# TSat0-AvionicsPCB_v12.net
KiCad netlist of a schematic drawn in EAGLE
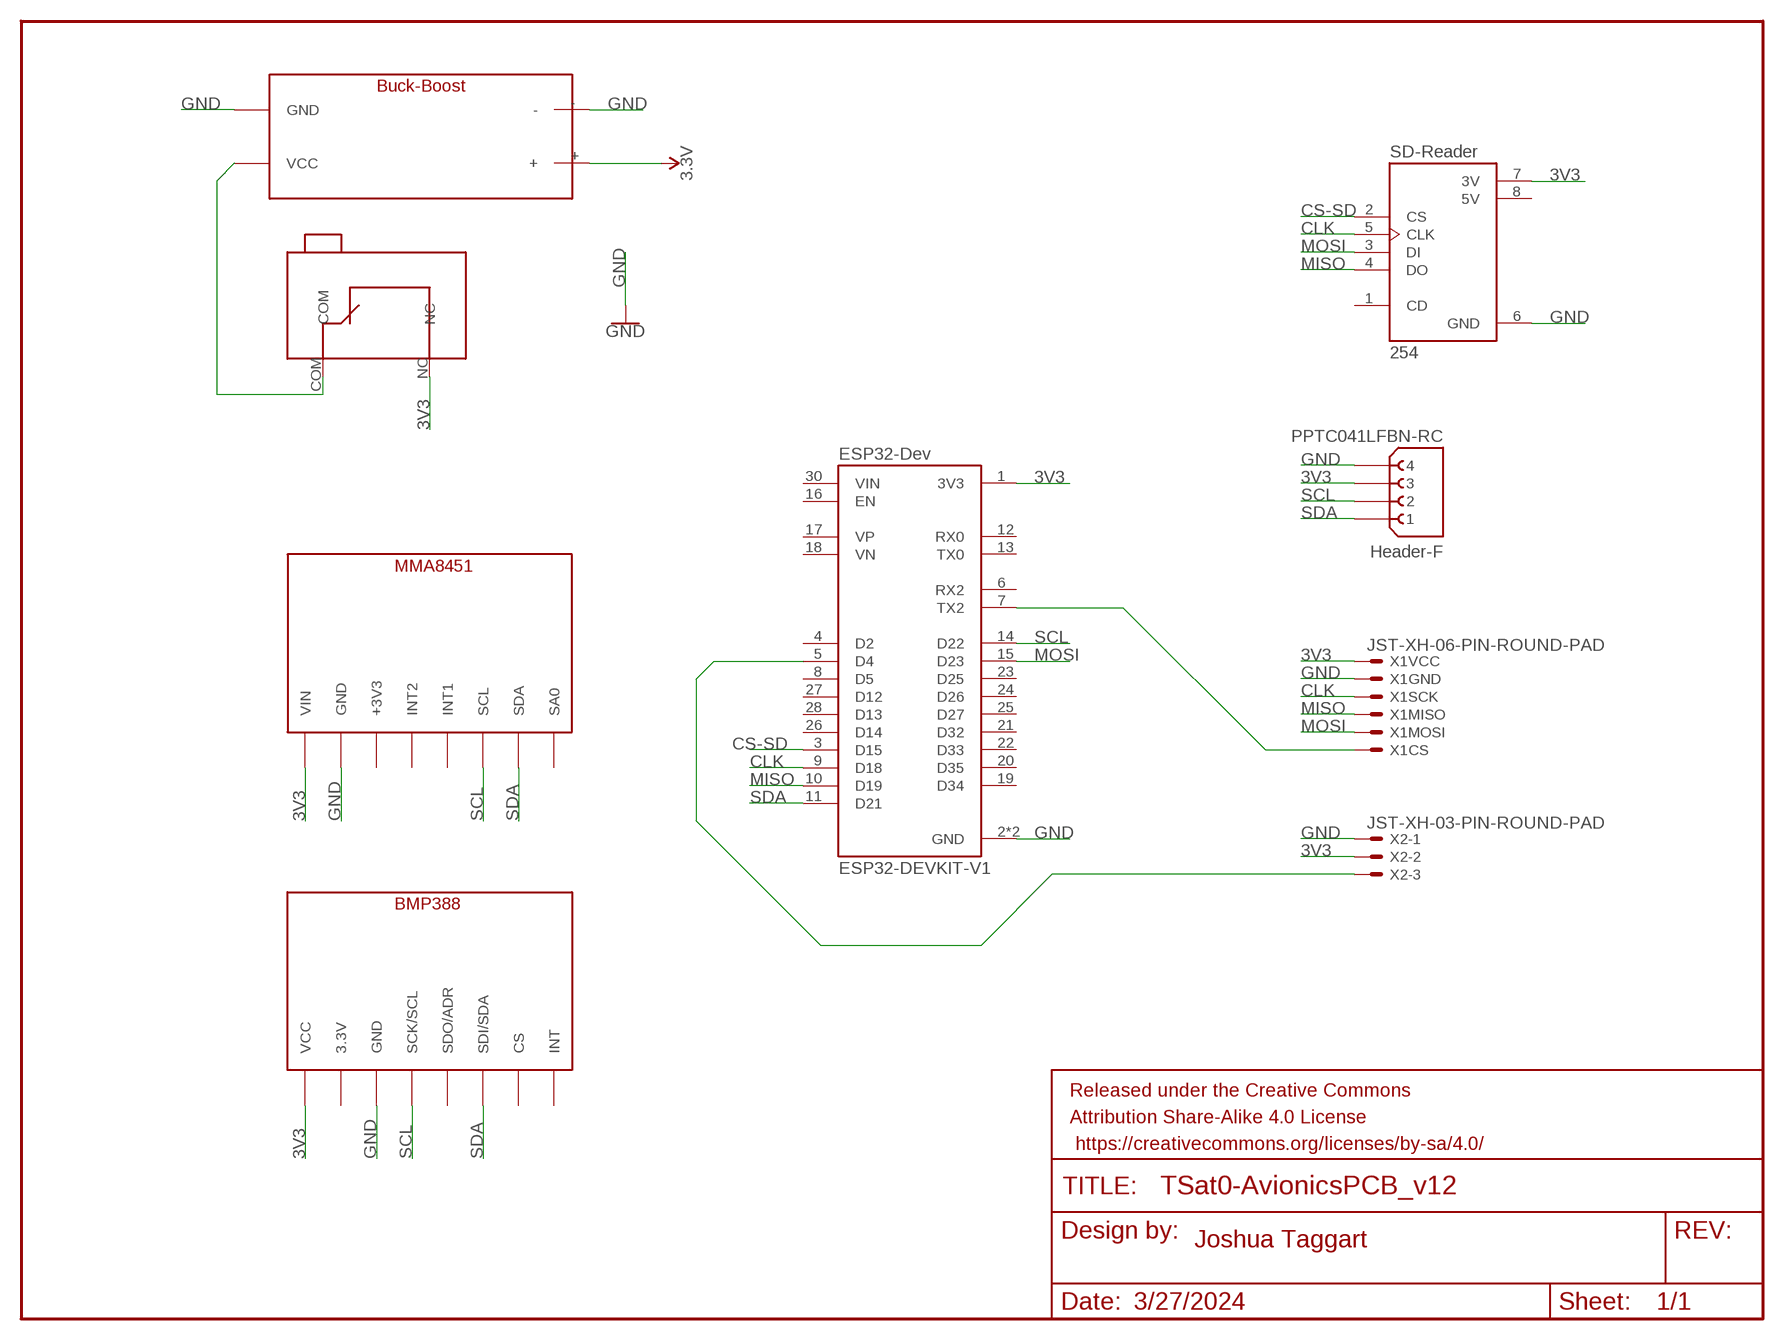
[diagram p0: schematic, sheet 1]

(export (version "E")
  (design (tool "Eeschema 10.0.6"))
  (components
    (comp (ref "BMP388")
      (value "BMP388")
      (footprint "eagle-import:BMP388-FP")
      (libsource (lib "eagle-import") (part "BMP388"))
    )
    (comp (ref "FRAME1")
      (value "FRAME-LETTERNO_PACKAGE")
      (footprint "eagle-import:DUMMY")
      (fields (field (name "DESIGNER") "Nobody"))
      (libsource (lib "eagle-import") (part "FRAME-LETTERNO_PACKAGE"))
    )
    (comp (ref "J1")
      (value "PPTC041LFBN-RC")
      (footprint "eagle-import:SULLINS_PPTC041LFBN-RC")
      (fields (field (name "MF") "Sullins Connector"))
      (libsource (lib "eagle-import") (part "PPTC041LFBN-RC"))
    )
    (comp (ref "MMA8451")
      (value "MMA8451")
      (footprint "eagle-import:MMA8451-FP")
      (libsource (lib "eagle-import") (part "MMA8451"))
    )
    (comp (ref "U$1")
      (value "BUCKBOOST-LIPO")
      (footprint "eagle-import:BUCKBOOST-FP")
      (libsource (lib "eagle-import") (part "BUCKBOOST-LIPO"))
    )
    (comp (ref "U$2")
      (value "OMRON-MICROSWITCH")
      (footprint "eagle-import:OMRON-MICROSWITCH-FP")
      (libsource (lib "eagle-import") (part "OMRON-MICROSWITCH"))
    )
    (comp (ref "U1")
      (value "ESP32-DEVKIT-V1")
      (footprint "eagle-import:MODULE_ESP32_DEVKIT_V1")
      (fields (field (name "MF") "Do it"))
      (libsource (lib "eagle-import") (part "ESP32-DEVKIT-V1"))
    )
    (comp (ref "U2")
      (value "254")
      (footprint "eagle-import:MODULE_254")
      (fields (field (name "MF") "Adafruit"))
      (libsource (lib "eagle-import") (part "254"))
    )
    (comp (ref "X1")
      (value "JST-XH-06-PIN-ROUND-PAD")
      (footprint "eagle-import:JST-XH-06-PACKAGE-ROUND-PAD")
      (libsource (lib "eagle-import") (part "JST-XH-06-PIN-ROUND-PAD"))
    )
    (comp (ref "X2")
      (value "JST-XH-03-PIN-ROUND-PAD")
      (footprint "eagle-import:JST-XH-03-PACKAGE-ROUND-PAD")
      (libsource (lib "eagle-import") (part "JST-XH-03-PIN-ROUND-PAD"))
    )
  )
  (nets
    (net (code "1") (name "/3V3") (class "Default")
      (node (ref "BMP388") (pin "VCC") (pinfunction "VCC_VCC") (pintype "bidirectional"))
      (node (ref "J1") (pin "3") (pinfunction "3_3") (pintype "passive"))
      (node (ref "MMA8451") (pin "VIN") (pinfunction "VIN_VIN") (pintype "bidirectional"))
      (node (ref "U$2") (pin "NC") (pinfunction "NC_NC") (pintype "bidirectional"))
      (node (ref "U1") (pin "1") (pinfunction "3V3_1") (pintype "output"))
      (node (ref "U2") (pin "7") (pinfunction "3V_7") (pintype "power_in"))
      (node (ref "X1") (pin "VCC") (pinfunction "S_VCC") (pintype "passive"))
      (node (ref "X2") (pin "2") (pinfunction "S_2") (pintype "passive"))
    )
    (net (code "2") (name "/5V") (class "Default")
      (node (ref "U2") (pin "8") (pinfunction "5V_8") (pintype "power_in"))
    )
    (net (code "3") (name "/CLK") (class "Default")
      (node (ref "U1") (pin "9") (pinfunction "D18_9") (pintype "bidirectional"))
      (node (ref "U2") (pin "5") (pinfunction "CLK_5") (pintype "input"))
      (node (ref "X1") (pin "SCK") (pinfunction "S_SCK") (pintype "passive"))
    )
    (net (code "4") (name "/CS-SD") (class "Default")
      (node (ref "U1") (pin "3") (pinfunction "D15_3") (pintype "bidirectional"))
      (node (ref "U2") (pin "2") (pinfunction "CS_2") (pintype "input"))
    )
    (net (code "5") (name "/MISO") (class "Default")
      (node (ref "U1") (pin "10") (pinfunction "D19_10") (pintype "bidirectional"))
      (node (ref "U2") (pin "4") (pinfunction "DO_4") (pintype "output"))
      (node (ref "X1") (pin "MISO") (pinfunction "S_MISO") (pintype "passive"))
    )
    (net (code "6") (name "/MOSI") (class "Default")
      (node (ref "U1") (pin "15") (pinfunction "D23_15") (pintype "bidirectional"))
      (node (ref "U2") (pin "3") (pinfunction "DI_3") (pintype "input"))
      (node (ref "X1") (pin "MOSI") (pinfunction "S_MOSI") (pintype "passive"))
    )
    (net (code "7") (name "/SCL") (class "Default")
      (node (ref "BMP388") (pin "SCK/SCL") (pinfunction "SCK/SCL_SCK/SCL") (pintype "bidirectional"))
      (node (ref "J1") (pin "2") (pinfunction "2_2") (pintype "passive"))
      (node (ref "MMA8451") (pin "SCL") (pinfunction "SCL_SCL") (pintype "bidirectional"))
      (node (ref "U1") (pin "14") (pinfunction "D22_14") (pintype "bidirectional"))
    )
    (net (code "8") (name "/SDA") (class "Default")
      (node (ref "BMP388") (pin "SDI/SDA") (pinfunction "SDI/SDA_SDI/SDA") (pintype "bidirectional"))
      (node (ref "J1") (pin "1") (pinfunction "1_1") (pintype "passive"))
      (node (ref "MMA8451") (pin "SDA") (pinfunction "SDA_SDA") (pintype "bidirectional"))
      (node (ref "U1") (pin "11") (pinfunction "D21_11") (pintype "bidirectional"))
    )
    (net (code "9") (name "3.3V") (class "Default")
      (node (ref "U$1") (pin "+") (pinfunction "+_+") (pintype "bidirectional"))
    )
    (net (code "10") (name "GND") (class "Default")
      (node (ref "BMP388") (pin "GND") (pinfunction "GND_GND") (pintype "bidirectional"))
      (node (ref "J1") (pin "4") (pinfunction "4_4") (pintype "passive"))
      (node (ref "MMA8451") (pin "GND") (pinfunction "GND_GND") (pintype "bidirectional"))
      (node (ref "U$1") (pin "-") (pinfunction "-_-") (pintype "bidirectional"))
      (node (ref "U$1") (pin "GND") (pinfunction "GND_GND") (pintype "bidirectional"))
      (node (ref "U1") (pin "2") (pinfunction "GND_2") (pintype "power_in"))
      (node (ref "U1") (pin "29") (pinfunction "GND_29") (pintype "power_in"))
      (node (ref "U2") (pin "6") (pinfunction "GND_6") (pintype "power_in"))
      (node (ref "X1") (pin "GND") (pinfunction "S_GND") (pintype "passive"))
      (node (ref "X2") (pin "1") (pinfunction "S_1") (pintype "passive"))
    )
    (net (code "11") (name "Net-(U$1-PadVCC)") (class "Default")
      (node (ref "U$1") (pin "VCC") (pinfunction "VCC_VCC") (pintype "bidirectional"))
      (node (ref "U$2") (pin "COM") (pinfunction "COM_COM") (pintype "bidirectional"))
    )
    (net (code "12") (name "Net-(U1-D4)") (class "Default")
      (node (ref "U1") (pin "5") (pinfunction "D4_5") (pintype "bidirectional"))
      (node (ref "X2") (pin "3") (pinfunction "S_3") (pintype "passive"))
    )
    (net (code "13") (name "Net-(U1-TX2)") (class "Default")
      (node (ref "U1") (pin "7") (pinfunction "TX2_7") (pintype "output"))
      (node (ref "X1") (pin "CS") (pinfunction "S_CS") (pintype "passive"))
    )
    (net (code "14") (name "unconnected-(BMP388-Pad3.3V)") (class "Default")
      (node (ref "BMP388") (pin "3.3V") (pinfunction "3.3V_3.3V") (pintype "bidirectional"))
    )
    (net (code "15") (name "unconnected-(BMP388-PadCS)") (class "Default")
      (node (ref "BMP388") (pin "CS") (pinfunction "CS_CS") (pintype "bidirectional"))
    )
    (net (code "16") (name "unconnected-(BMP388-PadINT)") (class "Default")
      (node (ref "BMP388") (pin "INT") (pinfunction "INT_INT") (pintype "bidirectional"))
    )
    (net (code "17") (name "unconnected-(BMP388-PadSDO{slash}ADR)") (class "Default")
      (node (ref "BMP388") (pin "SDO/ADR") (pinfunction "SDO/ADR_SDO/ADR") (pintype "bidirectional"))
    )
    (net (code "18") (name "unconnected-(MMA8451-Pad+3V3)") (class "Default")
      (node (ref "MMA8451") (pin "+3V3") (pinfunction "+3V3_+3V3") (pintype "bidirectional"))
    )
    (net (code "19") (name "unconnected-(MMA8451-PadINT1)") (class "Default")
      (node (ref "MMA8451") (pin "INT1") (pinfunction "INT1_INT1") (pintype "bidirectional"))
    )
    (net (code "20") (name "unconnected-(MMA8451-PadINT2)") (class "Default")
      (node (ref "MMA8451") (pin "INT2") (pinfunction "INT2_INT2") (pintype "bidirectional"))
    )
    (net (code "21") (name "unconnected-(MMA8451-PadSA0)") (class "Default")
      (node (ref "MMA8451") (pin "SA0") (pinfunction "SA0_SA0") (pintype "bidirectional"))
    )
    (net (code "22") (name "unconnected-(U1-D2-Pad4)") (class "Default")
      (node (ref "U1") (pin "4") (pinfunction "D2_4") (pintype "bidirectional"))
    )
    (net (code "23") (name "unconnected-(U1-D5-Pad8)") (class "Default")
      (node (ref "U1") (pin "8") (pinfunction "D5_8") (pintype "bidirectional"))
    )
    (net (code "24") (name "unconnected-(U1-D12-Pad27)") (class "Default")
      (node (ref "U1") (pin "27") (pinfunction "D12_27") (pintype "bidirectional"))
    )
    (net (code "25") (name "unconnected-(U1-D13-Pad28)") (class "Default")
      (node (ref "U1") (pin "28") (pinfunction "D13_28") (pintype "bidirectional"))
    )
    (net (code "26") (name "unconnected-(U1-D14-Pad26)") (class "Default")
      (node (ref "U1") (pin "26") (pinfunction "D14_26") (pintype "bidirectional"))
    )
    (net (code "27") (name "unconnected-(U1-D25-Pad23)") (class "Default")
      (node (ref "U1") (pin "23") (pinfunction "D25_23") (pintype "bidirectional"))
    )
    (net (code "28") (name "unconnected-(U1-D26-Pad24)") (class "Default")
      (node (ref "U1") (pin "24") (pinfunction "D26_24") (pintype "bidirectional"))
    )
    (net (code "29") (name "unconnected-(U1-D27-Pad25)") (class "Default")
      (node (ref "U1") (pin "25") (pinfunction "D27_25") (pintype "bidirectional"))
    )
    (net (code "30") (name "unconnected-(U1-D32-Pad21)") (class "Default")
      (node (ref "U1") (pin "21") (pinfunction "D32_21") (pintype "bidirectional"))
    )
    (net (code "31") (name "unconnected-(U1-D33-Pad22)") (class "Default")
      (node (ref "U1") (pin "22") (pinfunction "D33_22") (pintype "bidirectional"))
    )
    (net (code "32") (name "unconnected-(U1-D34-Pad19)") (class "Default")
      (node (ref "U1") (pin "19") (pinfunction "D34_19") (pintype "bidirectional"))
    )
    (net (code "33") (name "unconnected-(U1-D35-Pad20)") (class "Default")
      (node (ref "U1") (pin "20") (pinfunction "D35_20") (pintype "bidirectional"))
    )
    (net (code "34") (name "unconnected-(U1-EN-Pad16)") (class "Default")
      (node (ref "U1") (pin "16") (pinfunction "EN_16") (pintype "input"))
    )
    (net (code "35") (name "unconnected-(U1-RX0-Pad12)") (class "Default")
      (node (ref "U1") (pin "12") (pinfunction "RX0_12") (pintype "input"))
    )
    (net (code "36") (name "unconnected-(U1-RX2-Pad6)") (class "Default")
      (node (ref "U1") (pin "6") (pinfunction "RX2_6") (pintype "input"))
    )
    (net (code "37") (name "unconnected-(U1-TX0-Pad13)") (class "Default")
      (node (ref "U1") (pin "13") (pinfunction "TX0_13") (pintype "output"))
    )
    (net (code "38") (name "unconnected-(U1-VIN-Pad30)") (class "Default")
      (node (ref "U1") (pin "30") (pinfunction "VIN_30") (pintype "input"))
    )
    (net (code "39") (name "unconnected-(U1-VN-Pad18)") (class "Default")
      (node (ref "U1") (pin "18") (pinfunction "VN_18") (pintype "bidirectional"))
    )
    (net (code "40") (name "unconnected-(U1-VP-Pad17)") (class "Default")
      (node (ref "U1") (pin "17") (pinfunction "VP_17") (pintype "bidirectional"))
    )
    (net (code "41") (name "unconnected-(U2-CD-Pad1)") (class "Default")
      (node (ref "U2") (pin "1") (pinfunction "CD_1") (pintype "bidirectional"))
    )
  )
)
